# Expansion_Connector.net
KiCad netlist of a schematic drawn in Altium Designer
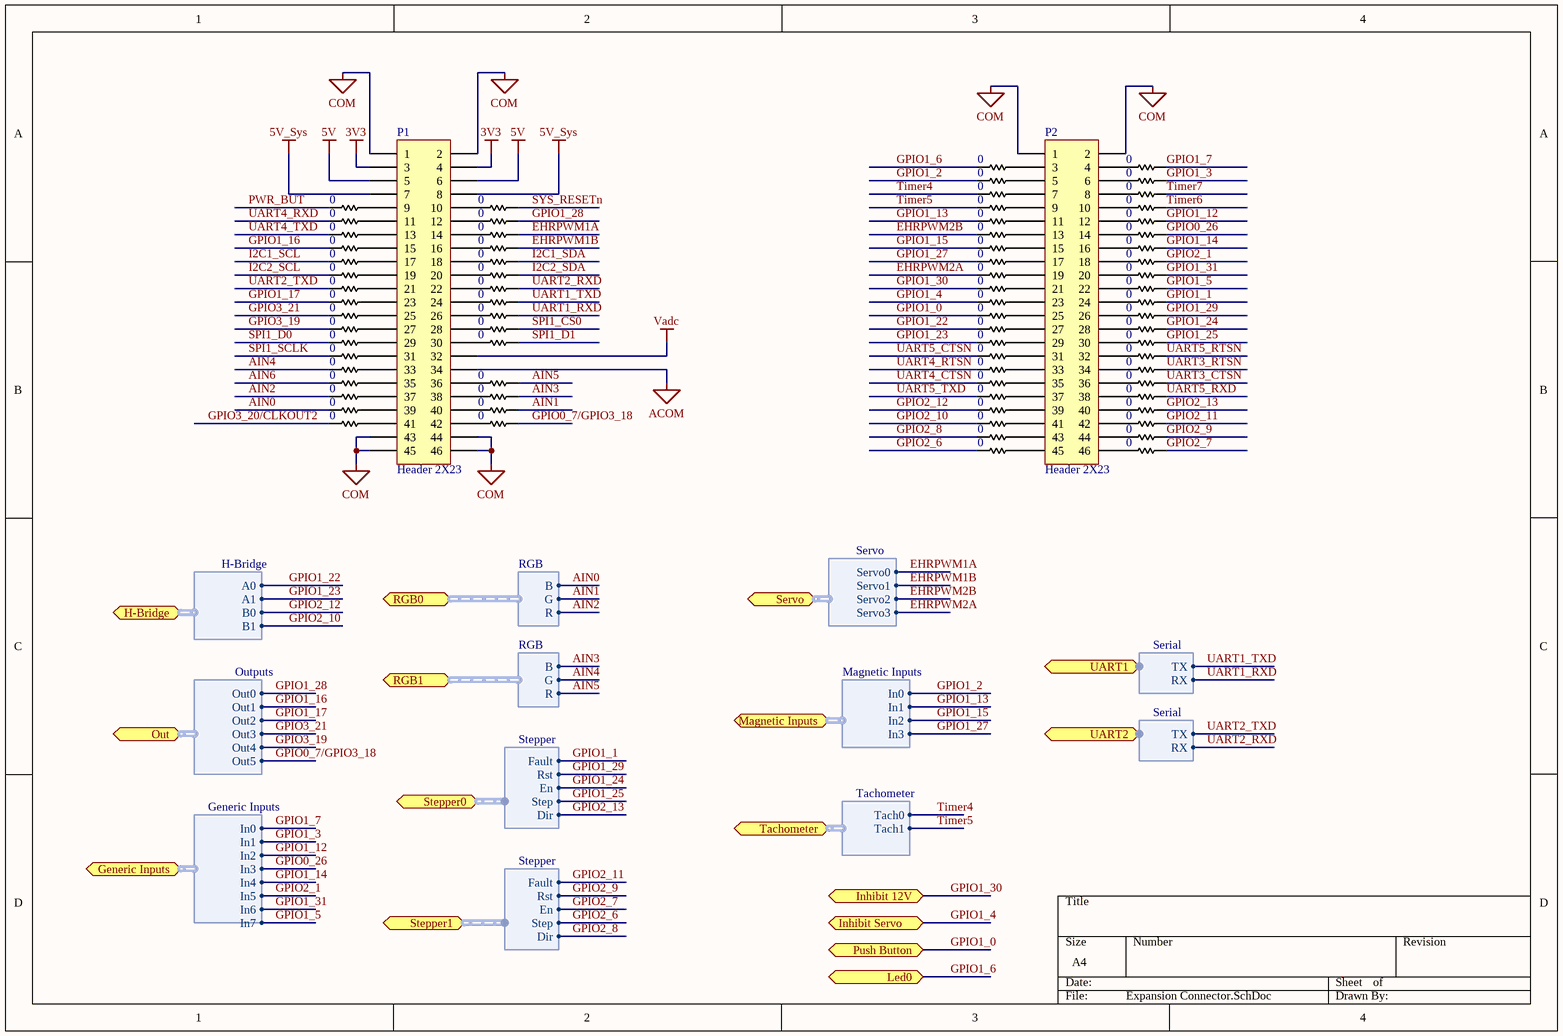
[diagram p0: Expansion Connector.SchDoc]

(export (version "E")
  (design (tool "Eeschema 10.0.6"))
  (components
    (comp (ref "J1")
      (value "0")
      (footprint "0805 - Resistor")
      (description "RES 0.0 OHM 1/8W JUMP 0805")
      (fields
        (field (name "PART NUMBER") "Jumper-0805")
        (field (name "MANUFACTURER") "Stackpole electronic")
        (field (name "CREATED BY") "Pier-Yves")
      )
      (libsource (lib "local") (part "Res"))
    )
    (comp (ref "J2")
      (value "0")
      (footprint "0805 - Resistor")
      (description "RES 0.0 OHM 1/8W JUMP 0805")
      (fields
        (field (name "PART NUMBER") "Jumper-0805")
        (field (name "MANUFACTURER") "Stackpole electronic")
        (field (name "CREATED BY") "Pier-Yves")
      )
      (libsource (lib "local") (part "Res"))
    )
    (comp (ref "J3")
      (value "0")
      (footprint "0805 - Resistor")
      (description "RES 0.0 OHM 1/8W JUMP 0805")
      (fields
        (field (name "PART NUMBER") "Jumper-0805")
        (field (name "MANUFACTURER") "Stackpole electronic")
        (field (name "CREATED BY") "Pier-Yves")
      )
      (libsource (lib "local") (part "Res"))
    )
    (comp (ref "J4")
      (value "0")
      (footprint "0805 - Resistor")
      (description "RES 0.0 OHM 1/8W JUMP 0805")
      (fields
        (field (name "PART NUMBER") "Jumper-0805")
        (field (name "MANUFACTURER") "Stackpole electronic")
        (field (name "CREATED BY") "Pier-Yves")
      )
      (libsource (lib "local") (part "Res"))
    )
    (comp (ref "J5")
      (value "0")
      (footprint "0805 - Resistor")
      (description "RES 0.0 OHM 1/8W JUMP 0805")
      (fields
        (field (name "PART NUMBER") "Jumper-0805")
        (field (name "MANUFACTURER") "Stackpole electronic")
        (field (name "CREATED BY") "Pier-Yves")
      )
      (libsource (lib "local") (part "Res"))
    )
    (comp (ref "J6")
      (value "0")
      (footprint "0805 - Resistor")
      (description "RES 0.0 OHM 1/8W JUMP 0805")
      (fields
        (field (name "PART NUMBER") "Jumper-0805")
        (field (name "MANUFACTURER") "Stackpole electronic")
        (field (name "CREATED BY") "Pier-Yves")
      )
      (libsource (lib "local") (part "Res"))
    )
    (comp (ref "J7")
      (value "0")
      (footprint "0805 - Resistor")
      (description "RES 0.0 OHM 1/8W JUMP 0805")
      (fields
        (field (name "PART NUMBER") "Jumper-0805")
        (field (name "MANUFACTURER") "Stackpole electronic")
        (field (name "CREATED BY") "Pier-Yves")
      )
      (libsource (lib "local") (part "Res"))
    )
    (comp (ref "J8")
      (value "0")
      (footprint "0805 - Resistor")
      (description "RES 0.0 OHM 1/8W JUMP 0805")
      (fields
        (field (name "PART NUMBER") "Jumper-0805")
        (field (name "MANUFACTURER") "Stackpole electronic")
        (field (name "CREATED BY") "Pier-Yves")
      )
      (libsource (lib "local") (part "Res"))
    )
    (comp (ref "J9")
      (value "0")
      (footprint "0805 - Resistor")
      (description "RES 0.0 OHM 1/8W JUMP 0805")
      (fields
        (field (name "PART NUMBER") "Jumper-0805")
        (field (name "MANUFACTURER") "Stackpole electronic")
        (field (name "CREATED BY") "Pier-Yves")
      )
      (libsource (lib "local") (part "Res"))
    )
    (comp (ref "J10")
      (value "0")
      (footprint "0805 - Resistor")
      (description "RES 0.0 OHM 1/8W JUMP 0805")
      (fields
        (field (name "PART NUMBER") "Jumper-0805")
        (field (name "MANUFACTURER") "Stackpole electronic")
        (field (name "CREATED BY") "Pier-Yves")
      )
      (libsource (lib "local") (part "Res"))
    )
    (comp (ref "J11")
      (value "0")
      (footprint "0805 - Resistor")
      (description "RES 0.0 OHM 1/8W JUMP 0805")
      (fields
        (field (name "PART NUMBER") "Jumper-0805")
        (field (name "MANUFACTURER") "Stackpole electronic")
        (field (name "CREATED BY") "Pier-Yves")
      )
      (libsource (lib "local") (part "Res"))
    )
    (comp (ref "J12")
      (value "0")
      (footprint "0805 - Resistor")
      (description "RES 0.0 OHM 1/8W JUMP 0805")
      (fields
        (field (name "PART NUMBER") "Jumper-0805")
        (field (name "MANUFACTURER") "Stackpole electronic")
        (field (name "CREATED BY") "Pier-Yves")
      )
      (libsource (lib "local") (part "Res"))
    )
    (comp (ref "J13")
      (value "0")
      (footprint "0805 - Resistor")
      (description "RES 0.0 OHM 1/8W JUMP 0805")
      (fields
        (field (name "PART NUMBER") "Jumper-0805")
        (field (name "MANUFACTURER") "Stackpole electronic")
        (field (name "CREATED BY") "Pier-Yves")
      )
      (libsource (lib "local") (part "Res"))
    )
    (comp (ref "J14")
      (value "0")
      (footprint "0805 - Resistor")
      (description "RES 0.0 OHM 1/8W JUMP 0805")
      (fields
        (field (name "PART NUMBER") "Jumper-0805")
        (field (name "MANUFACTURER") "Stackpole electronic")
        (field (name "CREATED BY") "Pier-Yves")
      )
      (libsource (lib "local") (part "Res"))
    )
    (comp (ref "J15")
      (value "0")
      (footprint "0805 - Resistor")
      (description "RES 0.0 OHM 1/8W JUMP 0805")
      (fields
        (field (name "PART NUMBER") "Jumper-0805")
        (field (name "MANUFACTURER") "Stackpole electronic")
        (field (name "CREATED BY") "Pier-Yves")
      )
      (libsource (lib "local") (part "Res"))
    )
    (comp (ref "J16")
      (value "0")
      (footprint "0805 - Resistor")
      (description "RES 0.0 OHM 1/8W JUMP 0805")
      (fields
        (field (name "PART NUMBER") "Jumper-0805")
        (field (name "MANUFACTURER") "Stackpole electronic")
        (field (name "CREATED BY") "Pier-Yves")
      )
      (libsource (lib "local") (part "Res"))
    )
    (comp (ref "J17")
      (value "0")
      (footprint "0805 - Resistor")
      (description "RES 0.0 OHM 1/8W JUMP 0805")
      (fields
        (field (name "PART NUMBER") "Jumper-0805")
        (field (name "MANUFACTURER") "Stackpole electronic")
        (field (name "CREATED BY") "Pier-Yves")
      )
      (libsource (lib "local") (part "Res"))
    )
    (comp (ref "J18")
      (value "0")
      (footprint "0805 - Resistor")
      (description "RES 0.0 OHM 1/8W JUMP 0805")
      (fields
        (field (name "PART NUMBER") "Jumper-0805")
        (field (name "MANUFACTURER") "Stackpole electronic")
        (field (name "CREATED BY") "Pier-Yves")
      )
      (libsource (lib "local") (part "Res"))
    )
    (comp (ref "J19")
      (value "0")
      (footprint "0805 - Resistor")
      (description "RES 0.0 OHM 1/8W JUMP 0805")
      (fields
        (field (name "PART NUMBER") "Jumper-0805")
        (field (name "MANUFACTURER") "Stackpole electronic")
        (field (name "CREATED BY") "Pier-Yves")
      )
      (libsource (lib "local") (part "Res"))
    )
    (comp (ref "J20")
      (value "0")
      (footprint "0805 - Resistor")
      (description "RES 0.0 OHM 1/8W JUMP 0805")
      (fields
        (field (name "PART NUMBER") "Jumper-0805")
        (field (name "MANUFACTURER") "Stackpole electronic")
        (field (name "CREATED BY") "Pier-Yves")
      )
      (libsource (lib "local") (part "Res"))
    )
    (comp (ref "J21")
      (value "0")
      (footprint "0805 - Resistor")
      (description "RES 0.0 OHM 1/8W JUMP 0805")
      (fields
        (field (name "PART NUMBER") "Jumper-0805")
        (field (name "MANUFACTURER") "Stackpole electronic")
        (field (name "CREATED BY") "Pier-Yves")
      )
      (libsource (lib "local") (part "Res"))
    )
    (comp (ref "J22")
      (value "0")
      (footprint "0805 - Resistor")
      (description "RES 0.0 OHM 1/8W JUMP 0805")
      (fields
        (field (name "PART NUMBER") "Jumper-0805")
        (field (name "MANUFACTURER") "Stackpole electronic")
        (field (name "CREATED BY") "Pier-Yves")
      )
      (libsource (lib "local") (part "Res"))
    )
    (comp (ref "J23")
      (value "0")
      (footprint "0805 - Resistor")
      (description "RES 0.0 OHM 1/8W JUMP 0805")
      (fields
        (field (name "PART NUMBER") "Jumper-0805")
        (field (name "MANUFACTURER") "Stackpole electronic")
        (field (name "CREATED BY") "Pier-Yves")
      )
      (libsource (lib "local") (part "Res"))
    )
    (comp (ref "J24")
      (value "0")
      (footprint "0805 - Resistor")
      (description "RES 0.0 OHM 1/8W JUMP 0805")
      (fields
        (field (name "PART NUMBER") "Jumper-0805")
        (field (name "MANUFACTURER") "Stackpole electronic")
        (field (name "CREATED BY") "Pier-Yves")
      )
      (libsource (lib "local") (part "Res"))
    )
    (comp (ref "J25")
      (value "0")
      (footprint "0805 - Resistor")
      (description "RES 0.0 OHM 1/8W JUMP 0805")
      (fields
        (field (name "PART NUMBER") "Jumper-0805")
        (field (name "MANUFACTURER") "Stackpole electronic")
        (field (name "CREATED BY") "Pier-Yves")
      )
      (libsource (lib "local") (part "Res"))
    )
    (comp (ref "J26")
      (value "0")
      (footprint "0805 - Resistor")
      (description "RES 0.0 OHM 1/8W JUMP 0805")
      (fields
        (field (name "PART NUMBER") "Jumper-0805")
        (field (name "MANUFACTURER") "Stackpole electronic")
        (field (name "CREATED BY") "Pier-Yves")
      )
      (libsource (lib "local") (part "Res"))
    )
    (comp (ref "J27")
      (value "0")
      (footprint "0805 - Resistor")
      (description "RES 0.0 OHM 1/8W JUMP 0805")
      (fields
        (field (name "PART NUMBER") "Jumper-0805")
        (field (name "MANUFACTURER") "Stackpole electronic")
        (field (name "CREATED BY") "Pier-Yves")
      )
      (libsource (lib "local") (part "Res"))
    )
    (comp (ref "J28")
      (value "0")
      (footprint "0805 - Resistor")
      (description "RES 0.0 OHM 1/8W JUMP 0805")
      (fields
        (field (name "PART NUMBER") "Jumper-0805")
        (field (name "MANUFACTURER") "Stackpole electronic")
        (field (name "CREATED BY") "Pier-Yves")
      )
      (libsource (lib "local") (part "Res"))
    )
    (comp (ref "J29")
      (value "0")
      (footprint "0805 - Resistor")
      (description "RES 0.0 OHM 1/8W JUMP 0805")
      (fields
        (field (name "PART NUMBER") "Jumper-0805")
        (field (name "MANUFACTURER") "Stackpole electronic")
        (field (name "CREATED BY") "Pier-Yves")
      )
      (libsource (lib "local") (part "Res"))
    )
    (comp (ref "J30")
      (value "0")
      (footprint "0805 - Resistor")
      (description "RES 0.0 OHM 1/8W JUMP 0805")
      (fields
        (field (name "PART NUMBER") "Jumper-0805")
        (field (name "MANUFACTURER") "Stackpole electronic")
        (field (name "CREATED BY") "Pier-Yves")
      )
      (libsource (lib "local") (part "Res"))
    )
    (comp (ref "J31")
      (value "0")
      (footprint "0805 - Resistor")
      (description "RES 0.0 OHM 1/8W JUMP 0805")
      (fields
        (field (name "PART NUMBER") "Jumper-0805")
        (field (name "MANUFACTURER") "Stackpole electronic")
        (field (name "CREATED BY") "Pier-Yves")
      )
      (libsource (lib "local") (part "Res"))
    )
    (comp (ref "J32")
      (value "0")
      (footprint "0805 - Resistor")
      (description "RES 0.0 OHM 1/8W JUMP 0805")
      (fields
        (field (name "PART NUMBER") "Jumper-0805")
        (field (name "MANUFACTURER") "Stackpole electronic")
        (field (name "CREATED BY") "Pier-Yves")
      )
      (libsource (lib "local") (part "Res"))
    )
    (comp (ref "J33")
      (value "0")
      (footprint "0805 - Resistor")
      (description "RES 0.0 OHM 1/8W JUMP 0805")
      (fields
        (field (name "PART NUMBER") "Jumper-0805")
        (field (name "MANUFACTURER") "Stackpole electronic")
        (field (name "CREATED BY") "Pier-Yves")
      )
      (libsource (lib "local") (part "Res"))
    )
    (comp (ref "J34")
      (value "0")
      (footprint "0805 - Resistor")
      (description "RES 0.0 OHM 1/8W JUMP 0805")
      (fields
        (field (name "PART NUMBER") "Jumper-0805")
        (field (name "MANUFACTURER") "Stackpole electronic")
        (field (name "CREATED BY") "Pier-Yves")
      )
      (libsource (lib "local") (part "Res"))
    )
    (comp (ref "J35")
      (value "0")
      (footprint "0805 - Resistor")
      (description "RES 0.0 OHM 1/8W JUMP 0805")
      (fields
        (field (name "PART NUMBER") "Jumper-0805")
        (field (name "MANUFACTURER") "Stackpole electronic")
        (field (name "CREATED BY") "Pier-Yves")
      )
      (libsource (lib "local") (part "Res"))
    )
    (comp (ref "J36")
      (value "0")
      (footprint "0805 - Resistor")
      (description "RES 0.0 OHM 1/8W JUMP 0805")
      (fields
        (field (name "PART NUMBER") "Jumper-0805")
        (field (name "MANUFACTURER") "Stackpole electronic")
        (field (name "CREATED BY") "Pier-Yves")
      )
      (libsource (lib "local") (part "Res"))
    )
    (comp (ref "J37")
      (value "0")
      (footprint "0805 - Resistor")
      (description "RES 0.0 OHM 1/8W JUMP 0805")
      (fields
        (field (name "PART NUMBER") "Jumper-0805")
        (field (name "MANUFACTURER") "Stackpole electronic")
        (field (name "CREATED BY") "Pier-Yves")
      )
      (libsource (lib "local") (part "Res"))
    )
    (comp (ref "J38")
      (value "0")
      (footprint "0805 - Resistor")
      (description "RES 0.0 OHM 1/8W JUMP 0805")
      (fields
        (field (name "PART NUMBER") "Jumper-0805")
        (field (name "MANUFACTURER") "Stackpole electronic")
        (field (name "CREATED BY") "Pier-Yves")
      )
      (libsource (lib "local") (part "Res"))
    )
    (comp (ref "J39")
      (value "0")
      (footprint "0805 - Resistor")
      (description "RES 0.0 OHM 1/8W JUMP 0805")
      (fields
        (field (name "PART NUMBER") "Jumper-0805")
        (field (name "MANUFACTURER") "Stackpole electronic")
        (field (name "CREATED BY") "Pier-Yves")
      )
      (libsource (lib "local") (part "Res"))
    )
    (comp (ref "J40")
      (value "0")
      (footprint "0805 - Resistor")
      (description "RES 0.0 OHM 1/8W JUMP 0805")
      (fields
        (field (name "PART NUMBER") "Jumper-0805")
        (field (name "MANUFACTURER") "Stackpole electronic")
        (field (name "CREATED BY") "Pier-Yves")
      )
      (libsource (lib "local") (part "Res"))
    )
    (comp (ref "J41")
      (value "0")
      (footprint "0805 - Resistor")
      (description "RES 0.0 OHM 1/8W JUMP 0805")
      (fields
        (field (name "PART NUMBER") "Jumper-0805")
        (field (name "MANUFACTURER") "Stackpole electronic")
        (field (name "CREATED BY") "Pier-Yves")
      )
      (libsource (lib "local") (part "Res"))
    )
    (comp (ref "J42")
      (value "0")
      (footprint "0805 - Resistor")
      (description "RES 0.0 OHM 1/8W JUMP 0805")
      (fields
        (field (name "PART NUMBER") "Jumper-0805")
        (field (name "MANUFACTURER") "Stackpole electronic")
        (field (name "CREATED BY") "Pier-Yves")
      )
      (libsource (lib "local") (part "Res"))
    )
    (comp (ref "J43")
      (value "0")
      (footprint "0805 - Resistor")
      (description "RES 0.0 OHM 1/8W JUMP 0805")
      (fields
        (field (name "PART NUMBER") "Jumper-0805")
        (field (name "MANUFACTURER") "Stackpole electronic")
        (field (name "CREATED BY") "Pier-Yves")
      )
      (libsource (lib "local") (part "Res"))
    )
    (comp (ref "J44")
      (value "0")
      (footprint "0805 - Resistor")
      (description "RES 0.0 OHM 1/8W JUMP 0805")
      (fields
        (field (name "PART NUMBER") "Jumper-0805")
        (field (name "MANUFACTURER") "Stackpole electronic")
        (field (name "CREATED BY") "Pier-Yves")
      )
      (libsource (lib "local") (part "Res"))
    )
    (comp (ref "J45")
      (value "0")
      (footprint "0805 - Resistor")
      (description "RES 0.0 OHM 1/8W JUMP 0805")
      (fields
        (field (name "PART NUMBER") "Jumper-0805")
        (field (name "MANUFACTURER") "Stackpole electronic")
        (field (name "CREATED BY") "Pier-Yves")
      )
      (libsource (lib "local") (part "Res"))
    )
    (comp (ref "J46")
      (value "0")
      (footprint "0805 - Resistor")
      (description "RES 0.0 OHM 1/8W JUMP 0805")
      (fields
        (field (name "PART NUMBER") "Jumper-0805")
        (field (name "MANUFACTURER") "Stackpole electronic")
        (field (name "CREATED BY") "Pier-Yves")
      )
      (libsource (lib "local") (part "Res"))
    )
    (comp (ref "J47")
      (value "0")
      (footprint "0805 - Resistor")
      (description "RES 0.0 OHM 1/8W JUMP 0805")
      (fields
        (field (name "PART NUMBER") "Jumper-0805")
        (field (name "MANUFACTURER") "Stackpole electronic")
        (field (name "CREATED BY") "Pier-Yves")
      )
      (libsource (lib "local") (part "Res"))
    )
    (comp (ref "J48")
      (value "0")
      (footprint "0805 - Resistor")
      (description "RES 0.0 OHM 1/8W JUMP 0805")
      (fields
        (field (name "PART NUMBER") "Jumper-0805")
        (field (name "MANUFACTURER") "Stackpole electronic")
        (field (name "CREATED BY") "Pier-Yves")
      )
      (libsource (lib "local") (part "Res"))
    )
    (comp (ref "J49")
      (value "0")
      (footprint "0805 - Resistor")
      (description "RES 0.0 OHM 1/8W JUMP 0805")
      (fields
        (field (name "PART NUMBER") "Jumper-0805")
        (field (name "MANUFACTURER") "Stackpole electronic")
        (field (name "CREATED BY") "Pier-Yves")
      )
      (libsource (lib "local") (part "Res"))
    )
    (comp (ref "J50")
      (value "0")
      (footprint "0805 - Resistor")
      (description "RES 0.0 OHM 1/8W JUMP 0805")
      (fields
        (field (name "PART NUMBER") "Jumper-0805")
        (field (name "MANUFACTURER") "Stackpole electronic")
        (field (name "CREATED BY") "Pier-Yves")
      )
      (libsource (lib "local") (part "Res"))
    )
    (comp (ref "J51")
      (value "0")
      (footprint "0805 - Resistor")
      (description "RES 0.0 OHM 1/8W JUMP 0805")
      (fields
        (field (name "PART NUMBER") "Jumper-0805")
        (field (name "MANUFACTURER") "Stackpole electronic")
        (field (name "CREATED BY") "Pier-Yves")
      )
      (libsource (lib "local") (part "Res"))
    )
    (comp (ref "J52")
      (value "0")
      (footprint "0805 - Resistor")
      (description "RES 0.0 OHM 1/8W JUMP 0805")
      (fields
        (field (name "PART NUMBER") "Jumper-0805")
        (field (name "MANUFACTURER") "Stackpole electronic")
        (field (name "CREATED BY") "Pier-Yves")
      )
      (libsource (lib "local") (part "Res"))
    )
    (comp (ref "J53")
      (value "0")
      (footprint "0805 - Resistor")
      (description "RES 0.0 OHM 1/8W JUMP 0805")
      (fields
        (field (name "PART NUMBER") "Jumper-0805")
        (field (name "MANUFACTURER") "Stackpole electronic")
        (field (name "CREATED BY") "Pier-Yves")
      )
      (libsource (lib "local") (part "Res"))
    )
    (comp (ref "J54")
      (value "0")
      (footprint "0805 - Resistor")
      (description "RES 0.0 OHM 1/8W JUMP 0805")
      (fields
        (field (name "PART NUMBER") "Jumper-0805")
        (field (name "MANUFACTURER") "Stackpole electronic")
        (field (name "CREATED BY") "Pier-Yves")
      )
      (libsource (lib "local") (part "Res"))
    )
    (comp (ref "J55")
      (value "0")
      (footprint "0805 - Resistor")
      (description "RES 0.0 OHM 1/8W JUMP 0805")
      (fields
        (field (name "PART NUMBER") "Jumper-0805")
        (field (name "MANUFACTURER") "Stackpole electronic")
        (field (name "CREATED BY") "Pier-Yves")
      )
      (libsource (lib "local") (part "Res"))
    )
    (comp (ref "J56")
      (value "0")
      (footprint "0805 - Resistor")
      (description "RES 0.0 OHM 1/8W JUMP 0805")
      (fields
        (field (name "PART NUMBER") "Jumper-0805")
        (field (name "MANUFACTURER") "Stackpole electronic")
        (field (name "CREATED BY") "Pier-Yves")
      )
      (libsource (lib "local") (part "Res"))
    )
    (comp (ref "J57")
      (value "0")
      (footprint "0805 - Resistor")
      (description "RES 0.0 OHM 1/8W JUMP 0805")
      (fields
        (field (name "PART NUMBER") "Jumper-0805")
        (field (name "MANUFACTURER") "Stackpole electronic")
        (field (name "CREATED BY") "Pier-Yves")
      )
      (libsource (lib "local") (part "Res"))
    )
    (comp (ref "J58")
      (value "0")
      (footprint "0805 - Resistor")
      (description "RES 0.0 OHM 1/8W JUMP 0805")
      (fields
        (field (name "PART NUMBER") "Jumper-0805")
        (field (name "MANUFACTURER") "Stackpole electronic")
        (field (name "CREATED BY") "Pier-Yves")
      )
      (libsource (lib "local") (part "Res"))
    )
    (comp (ref "J59")
      (value "0")
      (footprint "0805 - Resistor")
      (description "RES 0.0 OHM 1/8W JUMP 0805")
      (fields
        (field (name "PART NUMBER") "Jumper-0805")
        (field (name "MANUFACTURER") "Stackpole electronic")
        (field (name "CREATED BY") "Pier-Yves")
      )
      (libsource (lib "local") (part "Res"))
    )
    (comp (ref "J60")
      (value "0")
      (footprint "0805 - Resistor")
      (description "RES 0.0 OHM 1/8W JUMP 0805")
      (fields
        (field (name "PART NUMBER") "Jumper-0805")
        (field (name "MANUFACTURER") "Stackpole electronic")
        (field (name "CREATED BY") "Pier-Yves")
      )
      (libsource (lib "local") (part "Res"))
    )
    (comp (ref "J61")
      (value "0")
      (footprint "0805 - Resistor")
      (description "RES 0.0 OHM 1/8W JUMP 0805")
      (fields
        (field (name "PART NUMBER") "Jumper-0805")
        (field (name "MANUFACTURER") "Stackpole electronic")
        (field (name "CREATED BY") "Pier-Yves")
      )
      (libsource (lib "local") (part "Res"))
    )
    (comp (ref "J62")
      (value "0")
      (footprint "0805 - Resistor")
      (description "RES 0.0 OHM 1/8W JUMP 0805")
      (fields
        (field (name "PART NUMBER") "Jumper-0805")
        (field (name "MANUFACTURER") "Stackpole electronic")
        (field (name "CREATED BY") "Pier-Yves")
      )
      (libsource (lib "local") (part "Res"))
    )
    (comp (ref "J63")
      (value "0")
      (footprint "0805 - Resistor")
      (description "RES 0.0 OHM 1/8W JUMP 0805")
      (fields
        (field (name "PART NUMBER") "Jumper-0805")
        (field (name "MANUFACTURER") "Stackpole electronic")
        (field (name "CREATED BY") "Pier-Yves")
      )
      (libsource (lib "local") (part "Res"))
    )
    (comp (ref "J64")
      (value "0")
      (footprint "0805 - Resistor")
      (description "RES 0.0 OHM 1/8W JUMP 0805")
      (fields
        (field (name "PART NUMBER") "Jumper-0805")
        (field (name "MANUFACTURER") "Stackpole electronic")
        (field (name "CREATED BY") "Pier-Yves")
      )
      (libsource (lib "local") (part "Res"))
    )
    (comp (ref "J65")
      (value "0")
      (footprint "0805 - Resistor")
      (description "RES 0.0 OHM 1/8W JUMP 0805")
      (fields
        (field (name "PART NUMBER") "Jumper-0805")
        (field (name "MANUFACTURER") "Stackpole electronic")
        (field (name "CREATED BY") "Pier-Yves")
      )
      (libsource (lib "local") (part "Res"))
    )
    (comp (ref "J66")
      (value "0")
      (footprint "0805 - Resistor")
      (description "RES 0.0 OHM 1/8W JUMP 0805")
      (fields
        (field (name "PART NUMBER") "Jumper-0805")
        (field (name "MANUFACTURER") "Stackpole electronic")
        (field (name "CREATED BY") "Pier-Yves")
      )
      (libsource (lib "local") (part "Res"))
    )
    (comp (ref "J67")
      (value "0")
      (footprint "0805 - Resistor")
      (description "RES 0.0 OHM 1/8W JUMP 0805")
      (fields
        (field (name "PART NUMBER") "Jumper-0805")
        (field (name "MANUFACTURER") "Stackpole electronic")
        (field (name "CREATED BY") "Pier-Yves")
      )
      (libsource (lib "local") (part "Res"))
    )
    (comp (ref "J68")
      (value "0")
      (footprint "0805 - Resistor")
      (description "RES 0.0 OHM 1/8W JUMP 0805")
      (fields
        (field (name "PART NUMBER") "Jumper-0805")
        (field (name "MANUFACTURER") "Stackpole electronic")
        (field (name "CREATED BY") "Pier-Yves")
      )
      (libsource (lib "local") (part "Res"))
    )
    (comp (ref "J69")
      (value "0")
      (footprint "0805 - Resistor")
      (description "RES 0.0 OHM 1/8W JUMP 0805")
      (fields
        (field (name "PART NUMBER") "Jumper-0805")
        (field (name "MANUFACTURER") "Stackpole electronic")
        (field (name "CREATED BY") "Pier-Yves")
      )
      (libsource (lib "local") (part "Res"))
    )
    (comp (ref "J70")
      (value "0")
      (footprint "0805 - Resistor")
      (description "RES 0.0 OHM 1/8W JUMP 0805")
      (fields
        (field (name "PART NUMBER") "Jumper-0805")
        (field (name "MANUFACTURER") "Stackpole electronic")
        (field (name "CREATED BY") "Pier-Yves")
      )
      (libsource (lib "local") (part "Res"))
    )
    (comp (ref "J71")
      (value "0")
      (footprint "0805 - Resistor")
      (description "RES 0.0 OHM 1/8W JUMP 0805")
      (fields
        (field (name "PART NUMBER") "Jumper-0805")
        (field (name "MANUFACTURER") "Stackpole electronic")
        (field (name "CREATED BY") "Pier-Yves")
      )
      (libsource (lib "local") (part "Res"))
    )
    (comp (ref "J72")
      (value "0")
      (footprint "0805 - Resistor")
      (description "RES 0.0 OHM 1/8W JUMP 0805")
      (fields
        (field (name "PART NUMBER") "Jumper-0805")
        (field (name "MANUFACTURER") "Stackpole electronic")
        (field (name "CREATED BY") "Pier-Yves")
      )
      (libsource (lib "local") (part "Res"))
    )
    (comp (ref "J73")
      (value "0")
      (footprint "0805 - Resistor")
      (description "RES 0.0 OHM 1/8W JUMP 0805")
      (fields
        (field (name "PART NUMBER") "Jumper-0805")
        (field (name "MANUFACTURER") "Stackpole electronic")
        (field (name "CREATED BY") "Pier-Yves")
      )
      (libsource (lib "local") (part "Res"))
    )
    (comp (ref "J74")
      (value "0")
      (footprint "0805 - Resistor")
      (description "RES 0.0 OHM 1/8W JUMP 0805")
      (fields
        (field (name "PART NUMBER") "Jumper-0805")
        (field (name "MANUFACTURER") "Stackpole electronic")
        (field (name "CREATED BY") "Pier-Yves")
      )
      (libsource (lib "local") (part "Res"))
    )
    (comp (ref "J75")
      (value "0")
      (footprint "0805 - Resistor")
      (description "RES 0.0 OHM 1/8W JUMP 0805")
      (fields
        (field (name "PART NUMBER") "Jumper-0805")
        (field (name "MANUFACTURER") "Stackpole electronic")
        (field (name "CREATED BY") "Pier-Yves")
      )
      (libsource (lib "local") (part "Res"))
    )
    (comp (ref "J76")
      (value "0")
      (footprint "0805 - Resistor")
      (description "RES 0.0 OHM 1/8W JUMP 0805")
      (fields
        (field (name "PART NUMBER") "Jumper-0805")
        (field (name "MANUFACTURER") "Stackpole electronic")
        (field (name "CREATED BY") "Pier-Yves")
      )
      (libsource (lib "local") (part "Res"))
    )
    (comp (ref "P1")
      (value "Header 2X23")
      (footprint "Headers - 2x23 - Bottom")
      (fields
        (field (name "PART NUMBER") "Header-0.100-Generic-2x23")
        (field (name "MANUFACTURER") "Generic")
        (field (name "CREATED BY") "Pier-Yves")
      )
      (libsource (lib "local") (part "Header 2X23"))
    )
    (comp (ref "P2")
      (value "Header 2X23")
      (footprint "Headers - 2x23 - Bottom")
      (fields
        (field (name "PART NUMBER") "Header-0.100-Generic-2x23")
        (field (name "MANUFACTURER") "Generic")
        (field (name "CREATED BY") "Pier-Yves")
      )
      (libsource (lib "local") (part "Header 2X23"))
    )
  )
  (nets
    (net (code "11") (name "/AIN0") (class "Default")
      (node (ref "J65") (pin "2") (pinfunction "2_2") (pintype "passive"))
    )
    (net (code "12") (name "/AIN1") (class "Default")
      (node (ref "J66") (pin "1") (pinfunction "1_1") (pintype "passive"))
    )
    (net (code "13") (name "/AIN2") (class "Default")
      (node (ref "J61") (pin "2") (pinfunction "2_2") (pintype "passive"))
    )
    (net (code "14") (name "/AIN3") (class "Default")
      (node (ref "J62") (pin "1") (pinfunction "1_1") (pintype "passive"))
    )
    (net (code "15") (name "/AIN4") (class "Default")
      (node (ref "J54") (pin "2") (pinfunction "2_2") (pintype "passive"))
    )
    (net (code "16") (name "/AIN5") (class "Default")
      (node (ref "J58") (pin "1") (pinfunction "1_1") (pintype "passive"))
    )
    (net (code "17") (name "/AIN6") (class "Default")
      (node (ref "J57") (pin "2") (pinfunction "2_2") (pintype "passive"))
    )
    (net (code "18") (name "/EHRPWM1A") (class "Default")
      (node (ref "J16") (pin "1") (pinfunction "1_1") (pintype "passive"))
    )
    (net (code "19") (name "/EHRPWM1B") (class "Default")
      (node (ref "J20") (pin "1") (pinfunction "1_1") (pintype "passive"))
    )
    (net (code "20") (name "/EHRPWM2A") (class "Default")
      (node (ref "J29") (pin "2") (pinfunction "2_2") (pintype "passive"))
    )
    (net (code "21") (name "/EHRPWM2B") (class "Default")
      (node (ref "J17") (pin "2") (pinfunction "2_2") (pintype "passive"))
    )
    (net (code "22") (name "/GPIO0_7{slash}GPIO3_18") (class "Default")
      (node (ref "J70") (pin "1") (pinfunction "1_1") (pintype "passive"))
    )
    (net (code "23") (name "/GPIO0_26") (class "Default")
      (node (ref "J18") (pin "1") (pinfunction "1_1") (pintype "passive"))
    )
    (net (code "24") (name "/GPIO1_0") (class "Default")
      (node (ref "J41") (pin "2") (pinfunction "2_2") (pintype "passive"))
    )
    (net (code "25") (name "/GPIO1_1") (class "Default")
      (node (ref "J38") (pin "1") (pinfunction "1_1") (pintype "passive"))
    )
    (net (code "26") (name "/GPIO1_2") (class "Default")
      (node (ref "J3") (pin "2") (pinfunction "2_2") (pintype "passive"))
    )
    (net (code "27") (name "/GPIO1_3") (class "Default")
      (node (ref "J4") (pin "1") (pinfunction "1_1") (pintype "passive"))
    )
    (net (code "28") (name "/GPIO1_4") (class "Default")
      (node (ref "J37") (pin "2") (pinfunction "2_2") (pintype "passive"))
    )
    (net (code "29") (name "/GPIO1_5") (class "Default")
      (node (ref "J34") (pin "1") (pinfunction "1_1") (pintype "passive"))
    )
    (net (code "30") (name "/GPIO1_6") (class "Default")
      (node (ref "J1") (pin "2") (pinfunction "2_2") (pintype "passive"))
    )
    (net (code "31") (name "/GPIO1_7") (class "Default")
      (node (ref "J2") (pin "1") (pinfunction "1_1") (pintype "passive"))
    )
    (net (code "32") (name "/GPIO1_12") (class "Default")
      (node (ref "J14") (pin "1") (pinfunction "1_1") (pintype "passive"))
    )
    (net (code "33") (name "/GPIO1_13") (class "Default")
      (node (ref "J13") (pin "2") (pinfunction "2_2") (pintype "passive"))
    )
    (net (code "34") (name "/GPIO1_14") (class "Default")
      (node (ref "J22") (pin "1") (pinfunction "1_1") (pintype "passive"))
    )
    (net (code "35") (name "/GPIO1_15") (class "Default")
      (node (ref "J21") (pin "2") (pinfunction "2_2") (pintype "passive"))
    )
    (net (code "36") (name "/GPIO1_16") (class "Default")
      (node (ref "J19") (pin "2") (pinfunction "2_2") (pintype "passive"))
    )
    (net (code "37") (name "/GPIO1_17") (class "Default")
      (node (ref "J35") (pin "2") (pinfunction "2_2") (pintype "passive"))
    )
    (net (code "38") (name "/GPIO1_22") (class "Default")
      (node (ref "J45") (pin "2") (pinfunction "2_2") (pintype "passive"))
    )
    (net (code "39") (name "/GPIO1_23") (class "Default")
      (node (ref "J49") (pin "2") (pinfunction "2_2") (pintype "passive"))
    )
    (net (code "40") (name "/GPIO1_24") (class "Default")
      (node (ref "J46") (pin "1") (pinfunction "1_1") (pintype "passive"))
    )
    (net (code "41") (name "/GPIO1_25") (class "Default")
      (node (ref "J50") (pin "1") (pinfunction "1_1") (pintype "passive"))
    )
    (net (code "42") (name "/GPIO1_27") (class "Default")
      (node (ref "J25") (pin "2") (pinfunction "2_2") (pintype "passive"))
    )
    (net (code "43") (name "/GPIO1_28") (class "Default")
      (node (ref "J12") (pin "1") (pinfunction "1_1") (pintype "passive"))
    )
    (net (code "44") (name "/GPIO1_29") (class "Default")
      (node (ref "J42") (pin "1") (pinfunction "1_1") (pintype "passive"))
    )
    (net (code "45") (name "/GPIO1_30") (class "Default")
      (node (ref "J33") (pin "2") (pinfunction "2_2") (pintype "passive"))
    )
    (net (code "46") (name "/GPIO1_31") (class "Default")
      (node (ref "J30") (pin "1") (pinfunction "1_1") (pintype "passive"))
    )
    (net (code "47") (name "/GPIO2_1") (class "Default")
      (node (ref "J26") (pin "1") (pinfunction "1_1") (pintype "passive"))
    )
    (net (code "48") (name "/GPIO2_6") (class "Default")
      (node (ref "J75") (pin "2") (pinfunction "2_2") (pintype "passive"))
    )
    (net (code "49") (name "/GPIO2_7") (class "Default")
      (node (ref "J76") (pin "1") (pinfunction "1_1") (pintype "passive"))
    )
    (net (code "50") (name "/GPIO2_8") (class "Default")
      (node (ref "J73") (pin "2") (pinfunction "2_2") (pintype "passive"))
    )
    (net (code "51") (name "/GPIO2_9") (class "Default")
      (node (ref "J74") (pin "1") (pinfunction "1_1") (pintype "passive"))
    )
    (net (code "52") (name "/GPIO2_10") (class "Default")
      (node (ref "J71") (pin "2") (pinfunction "2_2") (pintype "passive"))
    )
    (net (code "53") (name "/GPIO2_11") (class "Default")
      (node (ref "J72") (pin "1") (pinfunction "1_1") (pintype "passive"))
    )
    (net (code "54") (name "/GPIO2_12") (class "Default")
      (node (ref "J67") (pin "2") (pinfunction "2_2") (pintype "passive"))
    )
    (net (code "55") (name "/GPIO2_13") (class "Default")
      (node (ref "J68") (pin "1") (pinfunction "1_1") (pintype "passive"))
    )
    (net (code "56") (name "/GPIO3_19") (class "Default")
      (node (ref "J43") (pin "2") (pinfunction "2_2") (pintype "passive"))
    )
    (net (code "57") (name "/GPIO3_20{slash}CLKOUT2") (class "Default")
      (node (ref "J69") (pin "2") (pinfunction "2_2") (pintype "passive"))
    )
    (net (code "58") (name "/GPIO3_21") (class "Default")
      (node (ref "J39") (pin "2") (pinfunction "2_2") (pintype "passive"))
    )
    (net (code "59") (name "/I2C1_SCL") (class "Default")
      (node (ref "J23") (pin "2") (pinfunction "2_2") (pintype "passive"))
    )
    (net (code "60") (name "/I2C1_SDA") (class "Default")
      (node (ref "J24") (pin "1") (pinfunction "1_1") (pintype "passive"))
    )
    (net (code "61") (name "/I2C2_SCL") (class "Default")
      (node (ref "J27") (pin "2") (pinfunction "2_2") (pintype "passive"))
    )
    (net (code "62") (name "/I2C2_SDA") (class "Default")
      (node (ref "J28") (pin "1") (pinfunction "1_1") (pintype "passive"))
    )
    (net (code "63") (name "/PWR_BUT") (class "Default")
      (node (ref "J7") (pin "2") (pinfunction "2_2") (pintype "passive"))
    )
    (net (code "64") (name "/SPI1_CS0") (class "Default")
      (node (ref "J44") (pin "1") (pinfunction "1_1") (pintype "passive"))
    )
    (net (code "65") (name "/SPI1_D0") (class "Default")
      (node (ref "J47") (pin "2") (pinfunction "2_2") (pintype "passive"))
    )
    (net (code "66") (name "/SPI1_D1") (class "Default")
      (node (ref "J48") (pin "1") (pinfunction "1_1") (pintype "passive"))
    )
    (net (code "67") (name "/SPI1_SCLK") (class "Default")
      (node (ref "J51") (pin "2") (pinfunction "2_2") (pintype "passive"))
    )
    (net (code "68") (name "/SYS_RESETn") (class "Default")
      (node (ref "J8") (pin "1") (pinfunction "1_1") (pintype "passive"))
    )
    (net (code "69") (name "/Timer4") (class "Default")
      (node (ref "J5") (pin "2") (pinfunction "2_2") (pintype "passive"))
    )
    (net (code "70") (name "/Timer5") (class "Default")
      (node (ref "J9") (pin "2") (pinfunction "2_2") (pintype "passive"))
    )
    (net (code "71") (name "/Timer6") (class "Default")
      (node (ref "J10") (pin "1") (pinfunction "1_1") (pintype "passive"))
    )
    (net (code "72") (name "/Timer7") (class "Default")
      (node (ref "J6") (pin "1") (pinfunction "1_1") (pintype "passive"))
    )
    (net (code "73") (name "/UART1_RXD") (class "Default")
      (node (ref "J40") (pin "1") (pinfunction "1_1") (pintype "passive"))
    )
    (net (code "74") (name "/UART1_TXD") (class "Default")
      (node (ref "J36") (pin "1") (pinfunction "1_1") (pintype "passive"))
    )
    (net (code "75") (name "/UART2_RXD") (class "Default")
      (node (ref "J32") (pin "1") (pinfunction "1_1") (pintype "passive"))
    )
    (net (code "76") (name "/UART2_TXD") (class "Default")
      (node (ref "J31") (pin "2") (pinfunction "2_2") (pintype "passive"))
    )
    (net (code "77") (name "/UART3_CTSN") (class "Default")
      (node (ref "J60") (pin "1") (pinfunction "1_1") (pintype "passive"))
    )
    (net (code "78") (name "/UART3_RTSN") (class "Default")
      (node (ref "J56") (pin "1") (pinfunction "1_1") (pintype "passive"))
    )
    (net (code "79") (name "/UART4_CTSN") (class "Default")
      (node (ref "J59") (pin "2") (pinfunction "2_2") (pintype "passive"))
    )
    (net (code "80") (name "/UART4_RTSN") (class "Default")
      (node (ref "J55") (pin "2") (pinfunction "2_2") (pintype "passive"))
    )
    (net (code "81") (name "/UART4_RXD") (class "Default")
      (node (ref "J11") (pin "2") (pinfunction "2_2") (pintype "passive"))
    )
    (net (code "82") (name "/UART4_TXD") (class "Default")
      (node (ref "J15") (pin "2") (pinfunction "2_2") (pintype "passive"))
    )
    (net (code "83") (name "/UART5_CTSN") (class "Default")
      (node (ref "J52") (pin "2") (pinfunction "2_2") (pintype "passive"))
    )
    (net (code "84") (name "/UART5_RTSN") (class "Default")
      (node (ref "J53") (pin "1") (pinfunction "1_1") (pintype "passive"))
    )
    (net (code "85") (name "/UART5_RXD") (class "Default")
      (node (ref "J64") (pin "1") (pinfunction "1_1") (pintype "passive"))
    )
    (net (code "86") (name "/UART5_TXD") (class "Default")
      (node (ref "J63") (pin "2") (pinfunction "2_2") (pintype "passive"))
    )
    (net (code "96") (name "3V3") (class "Default")
      (node (ref "P1") (pin "3") (pinfunction "3_3") (pintype "passive"))
      (node (ref "P1") (pin "4") (pinfunction "4_4") (pintype "passive"))
    )
    (net (code "97") (name "5V") (class "Default")
      (node (ref "P1") (pin "5") (pinfunction "5_5") (pintype "passive"))
      (node (ref "P1") (pin "6") (pinfunction "6_6") (pintype "passive"))
    )
    (net (code "98") (name "5V_Sys") (class "Default")
      (node (ref "P1") (pin "7") (pinfunction "7_7") (pintype "passive"))
      (node (ref "P1") (pin "8") (pinfunction "8_8") (pintype "passive"))
    )
    (net (code "99") (name "ACOM") (class "Default")
      (node (ref "P1") (pin "34") (pinfunction "34_34") (pintype "passive"))
    )
    (net (code "100") (name "COM") (class "Default")
      (node (ref "P1") (pin "1") (pinfunction "1_1") (pintype "passive"))
      (node (ref "P1") (pin "2") (pinfunction "2_2") (pintype "passive"))
      (node (ref "P1") (pin "43") (pinfunction "43_43") (pintype "passive"))
      (node (ref "P1") (pin "44") (pinfunction "44_44") (pintype "passive"))
      (node (ref "P1") (pin "45") (pinfunction "45_45") (pintype "passive"))
      (node (ref "P1") (pin "46") (pinfunction "46_46") (pintype "passive"))
      (node (ref "P2") (pin "1") (pinfunction "1_1") (pintype "passive"))
      (node (ref "P2") (pin "2") (pinfunction "2_2") (pintype "passive"))
    )
    (net (code "101") (name "Net-(J1-Pad1)") (class "Default")
      (node (ref "J1") (pin "1") (pinfunction "1_1") (pintype "passive"))
      (node (ref "P2") (pin "3") (pinfunction "3_3") (pintype "passive"))
    )
    (net (code "102") (name "Net-(J2-Pad2)") (class "Default")
      (node (ref "J2") (pin "2") (pinfunction "2_2") (pintype "passive"))
      (node (ref "P2") (pin "4") (pinfunction "4_4") (pintype "passive"))
    )
    (net (code "103") (name "Net-(J3-Pad1)") (class "Default")
      (node (ref "J3") (pin "1") (pinfunction "1_1") (pintype "passive"))
      (node (ref "P2") (pin "5") (pinfunction "5_5") (pintype "passive"))
    )
    (net (code "104") (name "Net-(J4-Pad2)") (class "Default")
      (node (ref "J4") (pin "2") (pinfunction "2_2") (pintype "passive"))
      (node (ref "P2") (pin "6") (pinfunction "6_6") (pintype "passive"))
    )
    (net (code "105") (name "Net-(J5-Pad1)") (class "Default")
      (node (ref "J5") (pin "1") (pinfunction "1_1") (pintype "passive"))
      (node (ref "P2") (pin "7") (pinfunction "7_7") (pintype "passive"))
    )
    (net (code "106") (name "Net-(J6-Pad2)") (class "Default")
      (node (ref "J6") (pin "2") (pinfunction "2_2") (pintype "passive"))
      (node (ref "P2") (pin "8") (pinfunction "8_8") (pintype "passive"))
    )
    (net (code "107") (name "Net-(J7-Pad1)") (class "Default")
      (node (ref "J7") (pin "1") (pinfunction "1_1") (pintype "passive"))
      (node (ref "P1") (pin "9") (pinfunction "9_9") (pintype "passive"))
    )
    (net (code "108") (name "Net-(J8-Pad2)") (class "Default")
      (node (ref "J8") (pin "2") (pinfunction "2_2") (pintype "passive"))
      (node (ref "P1") (pin "10") (pinfunction "10_10") (pintype "passive"))
    )
    (net (code "109") (name "Net-(J9-Pad1)") (class "Default")
      (node (ref "J9") (pin "1") (pinfunction "1_1") (pintype "passive"))
      (node (ref "P2") (pin "9") (pinfunction "9_9") (pintype "passive"))
    )
    (net (code "110") (name "Net-(J10-Pad2)") (class "Default")
      (node (ref "J10") (pin "2") (pinfunction "2_2") (pintype "passive"))
      (node (ref "P2") (pin "10") (pinfunction "10_10") (pintype "passive"))
    )
    (net (code "111") (name "Net-(J11-Pad1)") (class "Default")
      (node (ref "J11") (pin "1") (pinfunction "1_1") (pintype "passive"))
      (node (ref "P1") (pin "11") (pinfunction "11_11") (pintype "passive"))
    )
    (net (code "112") (name "Net-(J12-Pad2)") (class "Default")
      (node (ref "J12") (pin "2") (pinfunction "2_2") (pintype "passive"))
      (node (ref "P1") (pin "12") (pinfunction "12_12") (pintype "passive"))
    )
    (net (code "113") (name "Net-(J13-Pad1)") (class "Default")
      (node (ref "J13") (pin "1") (pinfunction "1_1") (pintype "passive"))
      (node (ref "P2") (pin "11") (pinfunction "11_11") (pintype "passive"))
    )
    (net (code "114") (name "Net-(J14-Pad2)") (class "Default")
      (node (ref "J14") (pin "2") (pinfunction "2_2") (pintype "passive"))
      (node (ref "P2") (pin "12") (pinfunction "12_12") (pintype "passive"))
    )
    (net (code "115") (name "Net-(J15-Pad1)") (class "Default")
      (node (ref "J15") (pin "1") (pinfunction "1_1") (pintype "passive"))
      (node (ref "P1") (pin "13") (pinfunction "13_13") (pintype "passive"))
    )
    (net (code "116") (name "Net-(J16-Pad2)") (class "Default")
      (node (ref "J16") (pin "2") (pinfunction "2_2") (pintype "passive"))
      (node (ref "P1") (pin "14") (pinfunction "14_14") (pintype "passive"))
    )
    (net (code "117") (name "Net-(J17-Pad1)") (class "Default")
      (node (ref "J17") (pin "1") (pinfunction "1_1") (pintype "passive"))
      (node (ref "P2") (pin "13") (pinfunction "13_13") (pintype "passive"))
    )
    (net (code "118") (name "Net-(J18-Pad2)") (class "Default")
      (node (ref "J18") (pin "2") (pinfunction "2_2") (pintype "passive"))
      (node (ref "P2") (pin "14") (pinfunction "14_14") (pintype "passive"))
    )
    (net (code "119") (name "Net-(J19-Pad1)") (class "Default")
      (node (ref "J19") (pin "1") (pinfunction "1_1") (pintype "passive"))
      (node (ref "P1") (pin "15") (pinfunction "15_15") (pintype "passive"))
    )
    (net (code "120") (name "Net-(J20-Pad2)") (class "Default")
      (node (ref "J20") (pin "2") (pinfunction "2_2") (pintype "passive"))
      (node (ref "P1") (pin "16") (pinfunction "16_16") (pintype "passive"))
    )
    (net (code "121") (name "Net-(J21-Pad1)") (class "Default")
      (node (ref "J21") (pin "1") (pinfunction "1_1") (pintype "passive"))
      (node (ref "P2") (pin "15") (pinfunction "15_15") (pintype "passive"))
    )
    (net (code "122") (name "Net-(J22-Pad2)") (class "Default")
      (node (ref "J22") (pin "2") (pinfunction "2_2") (pintype "passive"))
      (node (ref "P2") (pin "16") (pinfunction "16_16") (pintype "passive"))
    )
    (net (code "123") (name "Net-(J23-Pad1)") (class "Default")
      (node (ref "J23") (pin "1") (pinfunction "1_1") (pintype "passive"))
      (node (ref "P1") (pin "17") (pinfunction "17_17") (pintype "passive"))
    )
    (net (code "124") (name "Net-(J24-Pad2)") (class "Default")
      (node (ref "J24") (pin "2") (pinfunction "2_2") (pintype "passive"))
      (node (ref "P1") (pin "18") (pinfunction "18_18") (pintype "passive"))
    )
    (net (code "125") (name "Net-(J25-Pad1)") (class "Default")
      (node (ref "J25") (pin "1") (pinfunction "1_1") (pintype "passive"))
      (node (ref "P2") (pin "17") (pinfunction "17_17") (pintype "passive"))
    )
    (net (code "126") (name "Net-(J26-Pad2)") (class "Default")
      (node (ref "J26") (pin "2") (pinfunction "2_2") (pintype "passive"))
      (node (ref "P2") (pin "18") (pinfunction "18_18") (pintype "passive"))
    )
    (net (code "127") (name "Net-(J27-Pad1)") (class "Default")
      (node (ref "J27") (pin "1") (pinfunction "1_1") (pintype "passive"))
      (node (ref "P1") (pin "19") (pinfunction "19_19") (pintype "passive"))
    )
    (net (code "128") (name "Net-(J28-Pad2)") (class "Default")
      (node (ref "J28") (pin "2") (pinfunction "2_2") (pintype "passive"))
      (node (ref "P1") (pin "20") (pinfunction "20_20") (pintype "passive"))
    )
    (net (code "129") (name "Net-(J29-Pad1)") (class "Default")
      (node (ref "J29") (pin "1") (pinfunction "1_1") (pintype "passive"))
      (node (ref "P2") (pin "19") (pinfunction "19_19") (pintype "passive"))
    )
    (net (code "130") (name "Net-(J30-Pad2)") (class "Default")
      (node (ref "J30") (pin "2") (pinfunction "2_2") (pintype "passive"))
      (node (ref "P2") (pin "20") (pinfunction "20_20") (pintype "passive"))
    )
    (net (code "131") (name "Net-(J31-Pad1)") (class "Default")
      (node (ref "J31") (pin "1") (pinfunction "1_1") (pintype "passive"))
      (node (ref "P1") (pin "21") (pinfunction "21_21") (pintype "passive"))
    )
    (net (code "132") (name "Net-(J32-Pad2)") (class "Default")
      (node (ref "J32") (pin "2") (pinfunction "2_2") (pintype "passive"))
      (node (ref "P1") (pin "22") (pinfunction "22_22") (pintype "passive"))
    )
    (net (code "133") (name "Net-(J33-Pad1)") (class "Default")
      (node (ref "J33") (pin "1") (pinfunction "1_1") (pintype "passive"))
      (node (ref "P2") (pin "21") (pinfunction "21_21") (pintype "passive"))
    )
    (net (code "134") (name "Net-(J34-Pad2)") (class "Default")
      (node (ref "J34") (pin "2") (pinfunction "2_2") (pintype "passive"))
      (node (ref "P2") (pin "22") (pinfunction "22_22") (pintype "passive"))
    )
    (net (code "135") (name "Net-(J35-Pad1)") (class "Default")
      (node (ref "J35") (pin "1") (pinfunction "1_1") (pintype "passive"))
      (node (ref "P1") (pin "23") (pinfunction "23_23") (pintype "passive"))
    )
    (net (code "136") (name "Net-(J36-Pad2)") (class "Default")
      (node (ref "J36") (pin "2") (pinfunction "2_2") (pintype "passive"))
      (node (ref "P1") (pin "24") (pinfunction "24_24") (pintype "passive"))
    )
    (net (code "137") (name "Net-(J37-Pad1)") (class "Default")
      (node (ref "J37") (pin "1") (pinfunction "1_1") (pintype "passive"))
      (node (ref "P2") (pin "23") (pinfunction "23_23") (pintype "passive"))
    )
    (net (code "138") (name "Net-(J38-Pad2)") (class "Default")
      (node (ref "J38") (pin "2") (pinfunction "2_2") (pintype "passive"))
      (node (ref "P2") (pin "24") (pinfunction "24_24") (pintype "passive"))
    )
    (net (code "139") (name "Net-(J39-Pad1)") (class "Default")
      (node (ref "J39") (pin "1") (pinfunction "1_1") (pintype "passive"))
      (node (ref "P1") (pin "25") (pinfunction "25_25") (pintype "passive"))
    )
    (net (code "140") (name "Net-(J40-Pad2)") (class "Default")
      (node (ref "J40") (pin "2") (pinfunction "2_2") (pintype "passive"))
      (node (ref "P1") (pin "26") (pinfunction "26_26") (pintype "passive"))
    )
    (net (code "141") (name "Net-(J41-Pad1)") (class "Default")
      (node (ref "J41") (pin "1") (pinfunction "1_1") (pintype "passive"))
      (node (ref "P2") (pin "25") (pinfunction "25_25") (pintype "passive"))
    )
    (net (code "142") (name "Net-(J42-Pad2)") (class "Default")
      (node (ref "J42") (pin "2") (pinfunction "2_2") (pintype "passive"))
      (node (ref "P2") (pin "26") (pinfunction "26_26") (pintype "passive"))
    )
    (net (code "143") (name "Net-(J43-Pad1)") (class "Default")
      (node (ref "J43") (pin "1") (pinfunction "1_1") (pintype "passive"))
      (node (ref "P1") (pin "27") (pinfunction "27_27") (pintype "passive"))
    )
    (net (code "144") (name "Net-(J44-Pad2)") (class "Default")
      (node (ref "J44") (pin "2") (pinfunction "2_2") (pintype "passive"))
      (node (ref "P1") (pin "28") (pinfunction "28_28") (pintype "passive"))
    )
    (net (code "145") (name "Net-(J45-Pad1)") (class "Default")
      (node (ref "J45") (pin "1") (pinfunction "1_1") (pintype "passive"))
      (node (ref "P2") (pin "27") (pinfunction "27_27") (pintype "passive"))
    )
    (net (code "146") (name "Net-(J46-Pad2)") (class "Default")
      (node (ref "J46") (pin "2") (pinfunction "2_2") (pintype "passive"))
      (node (ref "P2") (pin "28") (pinfunction "28_28") (pintype "passive"))
    )
    (net (code "147") (name "Net-(J47-Pad1)") (class "Default")
      (node (ref "J47") (pin "1") (pinfunction "1_1") (pintype "passive"))
      (node (ref "P1") (pin "29") (pinfunction "29_29") (pintype "passive"))
    )
    (net (code "148") (name "Net-(J48-Pad2)") (class "Default")
      (node (ref "J48") (pin "2") (pinfunction "2_2") (pintype "passive"))
      (node (ref "P1") (pin "30") (pinfunction "30_30") (pintype "passive"))
    )
    (net (code "149") (name "Net-(J49-Pad1)") (class "Default")
      (node (ref "J49") (pin "1") (pinfunction "1_1") (pintype "passive"))
      (node (ref "P2") (pin "29") (pinfunction "29_29") (pintype "passive"))
    )
    (net (code "150") (name "Net-(J50-Pad2)") (class "Default")
      (node (ref "J50") (pin "2") (pinfunction "2_2") (pintype "passive"))
      (node (ref "P2") (pin "30") (pinfunction "30_30") (pintype "passive"))
    )
    (net (code "151") (name "Net-(J51-Pad1)") (class "Default")
      (node (ref "J51") (pin "1") (pinfunction "1_1") (pintype "passive"))
      (node (ref "P1") (pin "31") (pinfunction "31_31") (pintype "passive"))
    )
    (net (code "152") (name "Net-(J52-Pad1)") (class "Default")
      (node (ref "J52") (pin "1") (pinfunction "1_1") (pintype "passive"))
      (node (ref "P2") (pin "31") (pinfunction "31_31") (pintype "passive"))
    )
    (net (code "153") (name "Net-(J53-Pad2)") (class "Default")
      (node (ref "J53") (pin "2") (pinfunction "2_2") (pintype "passive"))
      (node (ref "P2") (pin "32") (pinfunction "32_32") (pintype "passive"))
    )
    (net (code "154") (name "Net-(J54-Pad1)") (class "Default")
      (node (ref "J54") (pin "1") (pinfunction "1_1") (pintype "passive"))
      (node (ref "P1") (pin "33") (pinfunction "33_33") (pintype "passive"))
    )
    (net (code "155") (name "Net-(J55-Pad1)") (class "Default")
      (node (ref "J55") (pin "1") (pinfunction "1_1") (pintype "passive"))
      (node (ref "P2") (pin "33") (pinfunction "33_33") (pintype "passive"))
    )
    (net (code "156") (name "Net-(J56-Pad2)") (class "Default")
      (node (ref "J56") (pin "2") (pinfunction "2_2") (pintype "passive"))
      (node (ref "P2") (pin "34") (pinfunction "34_34") (pintype "passive"))
    )
    (net (code "157") (name "Net-(J57-Pad1)") (class "Default")
      (node (ref "J57") (pin "1") (pinfunction "1_1") (pintype "passive"))
      (node (ref "P1") (pin "35") (pinfunction "35_35") (pintype "passive"))
    )
    (net (code "158") (name "Net-(J58-Pad2)") (class "Default")
      (node (ref "J58") (pin "2") (pinfunction "2_2") (pintype "passive"))
      (node (ref "P1") (pin "36") (pinfunction "36_36") (pintype "passive"))
    )
    (net (code "159") (name "Net-(J59-Pad1)") (class "Default")
      (node (ref "J59") (pin "1") (pinfunction "1_1") (pintype "passive"))
      (node (ref "P2") (pin "35") (pinfunction "35_35") (pintype "passive"))
    )
    (net (code "160") (name "Net-(J60-Pad2)") (class "Default")
      (node (ref "J60") (pin "2") (pinfunction "2_2") (pintype "passive"))
      (node (ref "P2") (pin "36") (pinfunction "36_36") (pintype "passive"))
    )
    (net (code "161") (name "Net-(J61-Pad1)") (class "Default")
      (node (ref "J61") (pin "1") (pinfunction "1_1") (pintype "passive"))
      (node (ref "P1") (pin "37") (pinfunction "37_37") (pintype "passive"))
    )
    (net (code "162") (name "Net-(J62-Pad2)") (class "Default")
      (node (ref "J62") (pin "2") (pinfunction "2_2") (pintype "passive"))
      (node (ref "P1") (pin "38") (pinfunction "38_38") (pintype "passive"))
    )
    (net (code "163") (name "Net-(J63-Pad1)") (class "Default")
      (node (ref "J63") (pin "1") (pinfunction "1_1") (pintype "passive"))
      (node (ref "P2") (pin "37") (pinfunction "37_37") (pintype "passive"))
    )
    (net (code "164") (name "Net-(J64-Pad2)") (class "Default")
      (node (ref "J64") (pin "2") (pinfunction "2_2") (pintype "passive"))
      (node (ref "P2") (pin "38") (pinfunction "38_38") (pintype "passive"))
    )
    (net (code "165") (name "Net-(J65-Pad1)") (class "Default")
      (node (ref "J65") (pin "1") (pinfunction "1_1") (pintype "passive"))
      (node (ref "P1") (pin "39") (pinfunction "39_39") (pintype "passive"))
    )
    (net (code "166") (name "Net-(J66-Pad2)") (class "Default")
      (node (ref "J66") (pin "2") (pinfunction "2_2") (pintype "passive"))
      (node (ref "P1") (pin "40") (pinfunction "40_40") (pintype "passive"))
    )
    (net (code "167") (name "Net-(J67-Pad1)") (class "Default")
      (node (ref "J67") (pin "1") (pinfunction "1_1") (pintype "passive"))
      (node (ref "P2") (pin "39") (pinfunction "39_39") (pintype "passive"))
    )
    (net (code "168") (name "Net-(J68-Pad2)") (class "Default")
      (node (ref "J68") (pin "2") (pinfunction "2_2") (pintype "passive"))
      (node (ref "P2") (pin "40") (pinfunction "40_40") (pintype "passive"))
    )
    (net (code "169") (name "Net-(J69-Pad1)") (class "Default")
      (node (ref "J69") (pin "1") (pinfunction "1_1") (pintype "passive"))
      (node (ref "P1") (pin "41") (pinfunction "41_41") (pintype "passive"))
    )
    (net (code "170") (name "Net-(J70-Pad2)") (class "Default")
      (node (ref "J70") (pin "2") (pinfunction "2_2") (pintype "passive"))
      (node (ref "P1") (pin "42") (pinfunction "42_42") (pintype "passive"))
    )
    (net (code "171") (name "Net-(J71-Pad1)") (class "Default")
      (node (ref "J71") (pin "1") (pinfunction "1_1") (pintype "passive"))
      (node (ref "P2") (pin "41") (pinfunction "41_41") (pintype "passive"))
    )
    (net (code "172") (name "Net-(J72-Pad2)") (class "Default")
      (node (ref "J72") (pin "2") (pinfunction "2_2") (pintype "passive"))
      (node (ref "P2") (pin "42") (pinfunction "42_42") (pintype "passive"))
    )
    (net (code "173") (name "Net-(J73-Pad1)") (class "Default")
      (node (ref "J73") (pin "1") (pinfunction "1_1") (pintype "passive"))
      (node (ref "P2") (pin "43") (pinfunction "43_43") (pintype "passive"))
    )
    (net (code "174") (name "Net-(J74-Pad2)") (class "Default")
      (node (ref "J74") (pin "2") (pinfunction "2_2") (pintype "passive"))
      (node (ref "P2") (pin "44") (pinfunction "44_44") (pintype "passive"))
    )
    (net (code "175") (name "Net-(J75-Pad1)") (class "Default")
      (node (ref "J75") (pin "1") (pinfunction "1_1") (pintype "passive"))
      (node (ref "P2") (pin "45") (pinfunction "45_45") (pintype "passive"))
    )
    (net (code "176") (name "Net-(J76-Pad2)") (class "Default")
      (node (ref "J76") (pin "2") (pinfunction "2_2") (pintype "passive"))
      (node (ref "P2") (pin "46") (pinfunction "46_46") (pintype "passive"))
    )
    (net (code "177") (name "Vadc") (class "Default")
      (node (ref "P1") (pin "32") (pinfunction "32_32") (pintype "passive"))
    )
  )
)
